# ef01.net
KiCad netlist of a schematic drawn in EAGLE
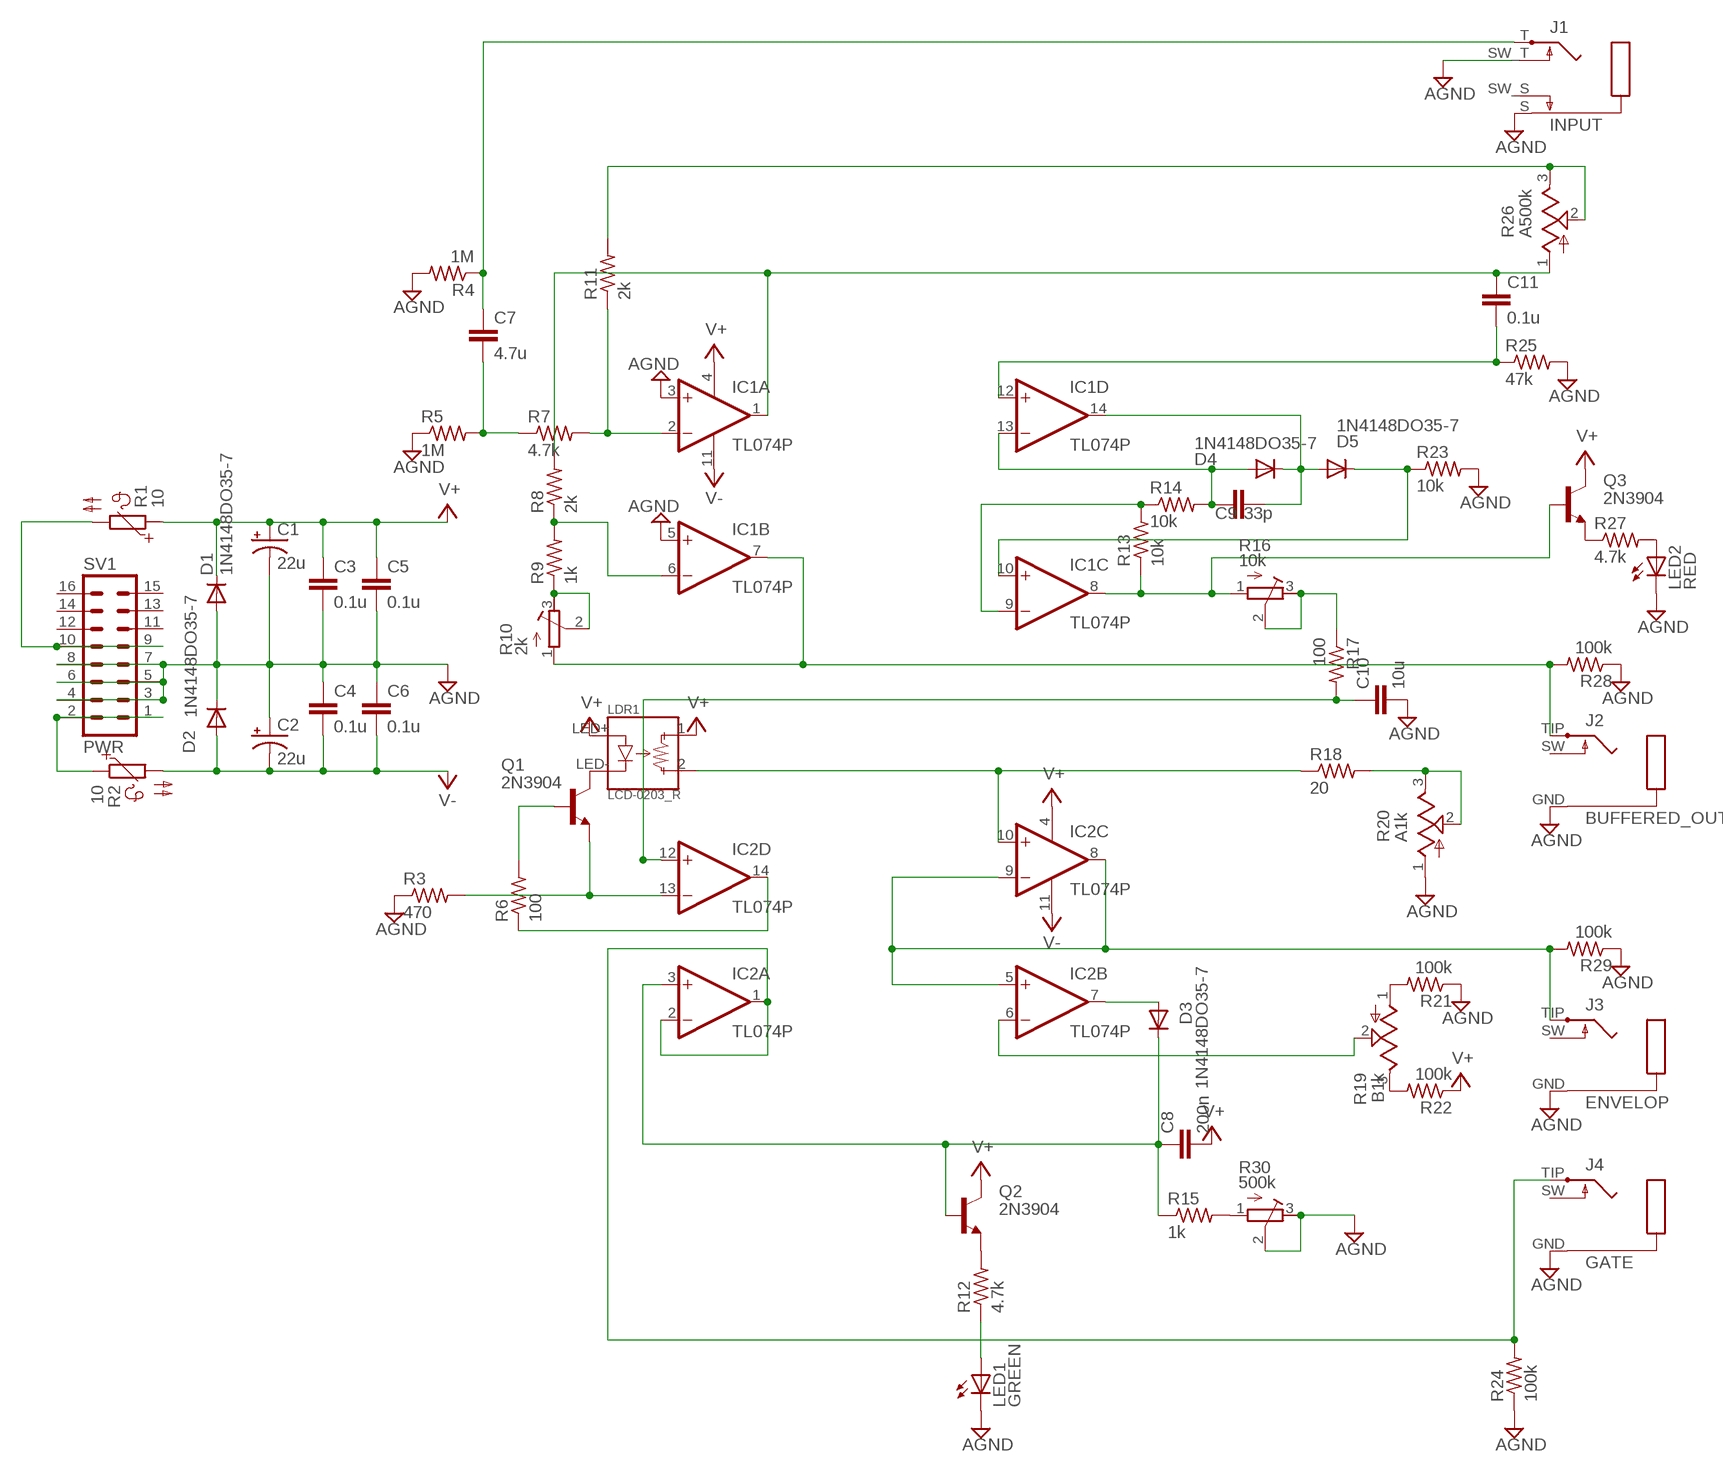
[diagram p0: schematic, sheet 1]

(export (version "E")
  (design (tool "Eeschema 10.0.6"))
  (components
    (comp (ref "C1")
      (value "22u")
      (footprint "eagle-import:E2,5-5")
      (libsource (lib "eagle-import") (part "CPOL-USE2.5-5"))
    )
    (comp (ref "C2")
      (value "22u")
      (footprint "eagle-import:E2,5-5")
      (libsource (lib "eagle-import") (part "CPOL-USE2.5-5"))
    )
    (comp (ref "C3")
      (value "0.1u")
      (footprint "eagle-import:C050-024X044")
      (libsource (lib "eagle-import") (part "C-EU050-024X044"))
    )
    (comp (ref "C4")
      (value "0.1u")
      (footprint "eagle-import:C050-024X044")
      (libsource (lib "eagle-import") (part "C-EU050-024X044"))
    )
    (comp (ref "C5")
      (value "0.1u")
      (footprint "eagle-import:C050-024X044")
      (libsource (lib "eagle-import") (part "C-EU050-024X044"))
    )
    (comp (ref "C6")
      (value "0.1u")
      (footprint "eagle-import:C050-024X044")
      (libsource (lib "eagle-import") (part "C-EU050-024X044"))
    )
    (comp (ref "C7")
      (value "4.7u")
      (footprint "eagle-import:C050-024X044")
      (libsource (lib "eagle-import") (part "C-EU050-024X044"))
    )
    (comp (ref "C8")
      (value "200n")
      (footprint "eagle-import:C050-024X044")
      (libsource (lib "eagle-import") (part "C-EU050-024X044"))
    )
    (comp (ref "C9")
      (value "33p")
      (footprint "eagle-import:C050-024X044")
      (libsource (lib "eagle-import") (part "C-EU050-024X044"))
    )
    (comp (ref "C10")
      (value "10u")
      (footprint "eagle-import:C050-024X044")
      (libsource (lib "eagle-import") (part "C-EU050-024X044"))
    )
    (comp (ref "C11")
      (value "0.1u")
      (footprint "eagle-import:C050-024X044")
      (libsource (lib "eagle-import") (part "C-EU050-024X044"))
    )
    (comp (ref "D1")
      (value "1N4148DO35-7")
      (footprint "eagle-import:DO35-7")
      (libsource (lib "eagle-import") (part "1N4148DO35-7"))
    )
    (comp (ref "D2")
      (value "1N4148DO35-7")
      (footprint "eagle-import:DO35-7")
      (libsource (lib "eagle-import") (part "1N4148DO35-7"))
    )
    (comp (ref "D3")
      (value "1N4148DO35-7")
      (footprint "eagle-import:DO35-7")
      (libsource (lib "eagle-import") (part "1N4148DO35-7"))
    )
    (comp (ref "D4")
      (value "1N4148DO35-7")
      (footprint "eagle-import:DO35-7")
      (libsource (lib "eagle-import") (part "1N4148DO35-7"))
    )
    (comp (ref "D5")
      (value "1N4148DO35-7")
      (footprint "eagle-import:DO35-7")
      (libsource (lib "eagle-import") (part "1N4148DO35-7"))
    )
    (comp (ref "IC1")
      (value "TL074P")
      (footprint "eagle-import:DIL14")
      (libsource (lib "eagle-import") (part "TL074P"))
    )
    (comp (ref "IC2")
      (value "TL074P")
      (footprint "eagle-import:DIL14")
      (libsource (lib "eagle-import") (part "TL074P"))
    )
    (comp (ref "J1")
      (value "INPUT")
      (footprint "eagle-import:ACJM-MHDR")
      (libsource (lib "eagle-import") (part "ACJM-MHDR"))
    )
    (comp (ref "J2")
      (value "BUFFERED_OUT")
      (footprint "eagle-import:35RAPC2AV")
      (libsource (lib "eagle-import") (part "35RAPC2AV"))
    )
    (comp (ref "J3")
      (value "ENVELOP")
      (footprint "eagle-import:35RAPC2AV")
      (libsource (lib "eagle-import") (part "35RAPC2AV"))
    )
    (comp (ref "J4")
      (value "GATE")
      (footprint "eagle-import:35RAPC2AV")
      (libsource (lib "eagle-import") (part "35RAPC2AV"))
    )
    (comp (ref "LDR1")
      (value "LCD-0203_R")
      (footprint "eagle-import:LCD-0203-R")
      (libsource (lib "eagle-import") (part "LCD-0203_R"))
    )
    (comp (ref "LED1")
      (value "GREEN")
      (footprint "eagle-import:LED3MM")
      (libsource (lib "eagle-import") (part "LED3MM"))
    )
    (comp (ref "LED2")
      (value "RED")
      (footprint "eagle-import:LED3MM")
      (libsource (lib "eagle-import") (part "LED3MM"))
    )
    (comp (ref "Q1")
      (value "2N3904")
      (footprint "eagle-import:TO92")
      (libsource (lib "eagle-import") (part "2N3904"))
    )
    (comp (ref "Q2")
      (value "2N3904")
      (footprint "eagle-import:TO92")
      (libsource (lib "eagle-import") (part "2N3904"))
    )
    (comp (ref "Q3")
      (value "2N3904")
      (footprint "eagle-import:TO92")
      (libsource (lib "eagle-import") (part "2N3904"))
    )
    (comp (ref "R1")
      (value "10")
      (footprint "eagle-import:P679")
      (libsource (lib "eagle-import") (part "PTC679"))
    )
    (comp (ref "R2")
      (value "10")
      (footprint "eagle-import:P679")
      (libsource (lib "eagle-import") (part "PTC679"))
    )
    (comp (ref "R3")
      (value "470")
      (footprint "eagle-import:0204_7")
      (libsource (lib "eagle-import") (part "R-US_0204/7"))
    )
    (comp (ref "R4")
      (value "1M")
      (footprint "eagle-import:0204_7")
      (libsource (lib "eagle-import") (part "R-US_0204/7"))
    )
    (comp (ref "R5")
      (value "1M")
      (footprint "eagle-import:0204_7")
      (libsource (lib "eagle-import") (part "R-US_0204/7"))
    )
    (comp (ref "R6")
      (value "100")
      (footprint "eagle-import:0204_7")
      (libsource (lib "eagle-import") (part "R-US_0204/7"))
    )
    (comp (ref "R7")
      (value "4.7k")
      (footprint "eagle-import:0204_7")
      (libsource (lib "eagle-import") (part "R-US_0204/7"))
    )
    (comp (ref "R8")
      (value "2k")
      (footprint "eagle-import:0204_7")
      (libsource (lib "eagle-import") (part "R-US_0204/7"))
    )
    (comp (ref "R9")
      (value "1k")
      (footprint "eagle-import:0204_7")
      (libsource (lib "eagle-import") (part "R-US_0204/7"))
    )
    (comp (ref "R10")
      (value "2k")
      (footprint "eagle-import:GF063P")
      (libsource (lib "eagle-import") (part "GFP063P"))
    )
    (comp (ref "R11")
      (value "2k")
      (footprint "eagle-import:0204_7")
      (libsource (lib "eagle-import") (part "R-US_0204/7"))
    )
    (comp (ref "R12")
      (value "4.7k")
      (footprint "eagle-import:0204_7")
      (libsource (lib "eagle-import") (part "R-US_0204/7"))
    )
    (comp (ref "R13")
      (value "10k")
      (footprint "eagle-import:0204_7")
      (libsource (lib "eagle-import") (part "R-US_0204/7"))
    )
    (comp (ref "R14")
      (value "10k")
      (footprint "eagle-import:0204_7")
      (libsource (lib "eagle-import") (part "R-US_0204/7"))
    )
    (comp (ref "R15")
      (value "1k")
      (footprint "eagle-import:0204_7")
      (libsource (lib "eagle-import") (part "R-US_0204/7"))
    )
    (comp (ref "R16")
      (value "10k")
      (footprint "eagle-import:GF063P")
      (libsource (lib "eagle-import") (part "GFP063P"))
    )
    (comp (ref "R17")
      (value "100")
      (footprint "eagle-import:0204_7")
      (libsource (lib "eagle-import") (part "R-US_0204/7"))
    )
    (comp (ref "R18")
      (value "20")
      (footprint "eagle-import:0204_7")
      (libsource (lib "eagle-import") (part "R-US_0204/7"))
    )
    (comp (ref "R19")
      (value "B1k")
      (footprint "eagle-import:RK097111")
      (libsource (lib "eagle-import") (part "RK097111"))
    )
    (comp (ref "R20")
      (value "A1k")
      (footprint "eagle-import:RK097111")
      (libsource (lib "eagle-import") (part "RK097111"))
    )
    (comp (ref "R21")
      (value "100k")
      (footprint "eagle-import:0204_7")
      (libsource (lib "eagle-import") (part "R-US_0204/7"))
    )
    (comp (ref "R22")
      (value "100k")
      (footprint "eagle-import:0204_7")
      (libsource (lib "eagle-import") (part "R-US_0204/7"))
    )
    (comp (ref "R23")
      (value "10k")
      (footprint "eagle-import:0204_7")
      (libsource (lib "eagle-import") (part "R-US_0204/7"))
    )
    (comp (ref "R24")
      (value "100k")
      (footprint "eagle-import:0204_7")
      (libsource (lib "eagle-import") (part "R-US_0204/7"))
    )
    (comp (ref "R25")
      (value "47k")
      (footprint "eagle-import:0204_7")
      (libsource (lib "eagle-import") (part "R-US_0204/7"))
    )
    (comp (ref "R26")
      (value "A500k")
      (footprint "eagle-import:RK097111")
      (libsource (lib "eagle-import") (part "RK097111"))
    )
    (comp (ref "R27")
      (value "4.7k")
      (footprint "eagle-import:0204_7")
      (libsource (lib "eagle-import") (part "R-US_0204/7"))
    )
    (comp (ref "R28")
      (value "100k")
      (footprint "eagle-import:0204_7")
      (libsource (lib "eagle-import") (part "R-US_0204/7"))
    )
    (comp (ref "R29")
      (value "100k")
      (footprint "eagle-import:0204_7")
      (libsource (lib "eagle-import") (part "R-US_0204/7"))
    )
    (comp (ref "R30")
      (value "500k")
      (footprint "eagle-import:GF063P")
      (libsource (lib "eagle-import") (part "GFP063P"))
    )
    (comp (ref "SV1")
      (value "PWR")
      (footprint "eagle-import:ML16")
      (libsource (lib "eagle-import") (part "ML16"))
    )
  )
  (nets
    (net (code "1") (name "AGND") (class "Default")
      (node (ref "C1") (pin "-") (pinfunction "-_-") (pintype "passive"))
      (node (ref "C10") (pin "2") (pinfunction "2_2") (pintype "passive"))
      (node (ref "C2") (pin "+") (pinfunction "+_+") (pintype "passive"))
      (node (ref "C3") (pin "2") (pinfunction "2_2") (pintype "passive"))
      (node (ref "C4") (pin "1") (pinfunction "1_1") (pintype "passive"))
      (node (ref "C5") (pin "2") (pinfunction "2_2") (pintype "passive"))
      (node (ref "C6") (pin "1") (pinfunction "1_1") (pintype "passive"))
      (node (ref "D1") (pin "A") (pinfunction "A_A") (pintype "passive"))
      (node (ref "D2") (pin "C") (pinfunction "C_C") (pintype "passive"))
      (node (ref "IC1") (pin "3") (pinfunction "+IN_3") (pintype "input"))
      (node (ref "IC1") (pin "5") (pinfunction "+IN_5") (pintype "input"))
      (node (ref "J1") (pin "S") (pinfunction "GND_S") (pintype "passive"))
      (node (ref "J1") (pin "SW_T") (pinfunction "T_SW_SW_T") (pintype "passive"))
      (node (ref "J2") (pin "GND") (pinfunction "GND_GND") (pintype "passive"))
      (node (ref "J3") (pin "GND") (pinfunction "GND_GND") (pintype "passive"))
      (node (ref "J4") (pin "GND") (pinfunction "GND_GND") (pintype "passive"))
      (node (ref "LED1") (pin "K") (pinfunction "C_K") (pintype "passive"))
      (node (ref "LED2") (pin "K") (pinfunction "C_K") (pintype "passive"))
      (node (ref "R20") (pin "1") (pinfunction "1_1") (pintype "passive"))
      (node (ref "R21") (pin "1") (pinfunction "1_1") (pintype "passive"))
      (node (ref "R23") (pin "2") (pinfunction "2_2") (pintype "passive"))
      (node (ref "R24") (pin "1") (pinfunction "1_1") (pintype "passive"))
      (node (ref "R25") (pin "2") (pinfunction "2_2") (pintype "passive"))
      (node (ref "R28") (pin "1") (pinfunction "1_1") (pintype "passive"))
      (node (ref "R29") (pin "1") (pinfunction "1_1") (pintype "passive"))
      (node (ref "R3") (pin "1") (pinfunction "1_1") (pintype "passive"))
      (node (ref "R30") (pin "2") (pinfunction "2_2") (pintype "passive"))
      (node (ref "R30") (pin "3") (pinfunction "3_3") (pintype "passive"))
      (node (ref "R4") (pin "2") (pinfunction "2_2") (pintype "passive"))
      (node (ref "R5") (pin "1") (pinfunction "1_1") (pintype "passive"))
      (node (ref "SV1") (pin "3") (pinfunction "3_3") (pintype "passive"))
      (node (ref "SV1") (pin "4") (pinfunction "4_4") (pintype "passive"))
      (node (ref "SV1") (pin "5") (pinfunction "5_5") (pintype "passive"))
      (node (ref "SV1") (pin "6") (pinfunction "6_6") (pintype "passive"))
      (node (ref "SV1") (pin "7") (pinfunction "7_7") (pintype "passive"))
      (node (ref "SV1") (pin "8") (pinfunction "8_8") (pintype "passive"))
    )
    (net (code "2") (name "Net-(C7-Pad2)") (class "Default")
      (node (ref "C7") (pin "2") (pinfunction "2_2") (pintype "passive"))
      (node (ref "R5") (pin "2") (pinfunction "2_2") (pintype "passive"))
      (node (ref "R7") (pin "1") (pinfunction "1_1") (pintype "passive"))
    )
    (net (code "3") (name "Net-(IC1A--IN)") (class "Default")
      (node (ref "IC1") (pin "2") (pinfunction "-IN_2") (pintype "input"))
      (node (ref "R11") (pin "1") (pinfunction "1_1") (pintype "passive"))
      (node (ref "R7") (pin "2") (pinfunction "2_2") (pintype "passive"))
    )
    (net (code "4") (name "Net-(IC1A-OUT)") (class "Default")
      (node (ref "C11") (pin "1") (pinfunction "1_1") (pintype "passive"))
      (node (ref "IC1") (pin "1") (pinfunction "OUT_1") (pintype "output"))
      (node (ref "R26") (pin "1") (pinfunction "1_1") (pintype "passive"))
      (node (ref "R8") (pin "2") (pinfunction "2_2") (pintype "passive"))
    )
    (net (code "5") (name "Net-(IC1B--IN)") (class "Default")
      (node (ref "IC1") (pin "6") (pinfunction "-IN_6") (pintype "input"))
      (node (ref "R8") (pin "1") (pinfunction "1_1") (pintype "passive"))
      (node (ref "R9") (pin "2") (pinfunction "2_2") (pintype "passive"))
    )
    (net (code "6") (name "Net-(IC1B-OUT)") (class "Default")
      (node (ref "IC1") (pin "7") (pinfunction "OUT_7") (pintype "output"))
      (node (ref "J2") (pin "TIP") (pinfunction "TIP_TIP") (pintype "passive"))
      (node (ref "R10") (pin "1") (pinfunction "1_1") (pintype "passive"))
      (node (ref "R28") (pin "2") (pinfunction "2_2") (pintype "passive"))
    )
    (net (code "7") (name "Net-(IC1C-+IN)") (class "Default")
      (node (ref "D5") (pin "C") (pinfunction "C_C") (pintype "passive"))
      (node (ref "IC1") (pin "10") (pinfunction "+IN_10") (pintype "input"))
      (node (ref "R23") (pin "1") (pinfunction "1_1") (pintype "passive"))
    )
    (net (code "8") (name "Net-(IC1C--IN)") (class "Default")
      (node (ref "IC1") (pin "9") (pinfunction "-IN_9") (pintype "input"))
      (node (ref "R13") (pin "2") (pinfunction "2_2") (pintype "passive"))
      (node (ref "R14") (pin "1") (pinfunction "1_1") (pintype "passive"))
    )
    (net (code "9") (name "Net-(IC1C-OUT)") (class "Default")
      (node (ref "IC1") (pin "8") (pinfunction "OUT_8") (pintype "output"))
      (node (ref "Q3") (pin "2") (pinfunction "B_2") (pintype "passive"))
      (node (ref "R13") (pin "1") (pinfunction "1_1") (pintype "passive"))
      (node (ref "R16") (pin "1") (pinfunction "1_1") (pintype "passive"))
    )
    (net (code "10") (name "Net-(IC1D-+IN)") (class "Default")
      (node (ref "C11") (pin "2") (pinfunction "2_2") (pintype "passive"))
      (node (ref "IC1") (pin "12") (pinfunction "+IN_12") (pintype "input"))
      (node (ref "R25") (pin "1") (pinfunction "1_1") (pintype "passive"))
    )
    (net (code "11") (name "Net-(IC1D--IN)") (class "Default")
      (node (ref "C9") (pin "1") (pinfunction "1_1") (pintype "passive"))
      (node (ref "D4") (pin "A") (pinfunction "A_A") (pintype "passive"))
      (node (ref "IC1") (pin "13") (pinfunction "-IN_13") (pintype "input"))
      (node (ref "R14") (pin "2") (pinfunction "2_2") (pintype "passive"))
    )
    (net (code "12") (name "Net-(IC1D-OUT)") (class "Default")
      (node (ref "C9") (pin "2") (pinfunction "2_2") (pintype "passive"))
      (node (ref "D4") (pin "C") (pinfunction "C_C") (pintype "passive"))
      (node (ref "D5") (pin "A") (pinfunction "A_A") (pintype "passive"))
      (node (ref "IC1") (pin "14") (pinfunction "OUT_14") (pintype "output"))
    )
    (net (code "13") (name "Net-(IC2A-+IN)") (class "Default")
      (node (ref "C8") (pin "1") (pinfunction "1_1") (pintype "passive"))
      (node (ref "D3") (pin "C") (pinfunction "C_C") (pintype "passive"))
      (node (ref "IC2") (pin "3") (pinfunction "+IN_3") (pintype "input"))
      (node (ref "Q2") (pin "2") (pinfunction "B_2") (pintype "passive"))
      (node (ref "R15") (pin "1") (pinfunction "1_1") (pintype "passive"))
    )
    (net (code "14") (name "Net-(IC2A--IN)") (class "Default")
      (node (ref "IC2") (pin "1") (pinfunction "OUT_1") (pintype "output"))
      (node (ref "IC2") (pin "2") (pinfunction "-IN_2") (pintype "input"))
      (node (ref "J4") (pin "TIP") (pinfunction "TIP_TIP") (pintype "passive"))
      (node (ref "R24") (pin "2") (pinfunction "2_2") (pintype "passive"))
    )
    (net (code "15") (name "Net-(IC2B-+IN)") (class "Default")
      (node (ref "IC2") (pin "5") (pinfunction "+IN_5") (pintype "input"))
      (node (ref "IC2") (pin "8") (pinfunction "OUT_8") (pintype "output"))
      (node (ref "IC2") (pin "9") (pinfunction "-IN_9") (pintype "input"))
      (node (ref "J3") (pin "TIP") (pinfunction "TIP_TIP") (pintype "passive"))
      (node (ref "R29") (pin "2") (pinfunction "2_2") (pintype "passive"))
    )
    (net (code "16") (name "Net-(IC2B--IN)") (class "Default")
      (node (ref "IC2") (pin "6") (pinfunction "-IN_6") (pintype "input"))
      (node (ref "R19") (pin "2") (pinfunction "2_2") (pintype "passive"))
    )
    (net (code "17") (name "Net-(IC2B-OUT)") (class "Default")
      (node (ref "D3") (pin "A") (pinfunction "A_A") (pintype "passive"))
      (node (ref "IC2") (pin "7") (pinfunction "OUT_7") (pintype "output"))
    )
    (net (code "18") (name "Net-(IC2C-+IN)") (class "Default")
      (node (ref "IC2") (pin "10") (pinfunction "+IN_10") (pintype "input"))
      (node (ref "LDR1") (pin "2") (pinfunction "2_2") (pintype "passive"))
      (node (ref "R18") (pin "1") (pinfunction "1_1") (pintype "passive"))
    )
    (net (code "19") (name "Net-(IC2D-+IN)") (class "Default")
      (node (ref "C10") (pin "1") (pinfunction "1_1") (pintype "passive"))
      (node (ref "IC2") (pin "12") (pinfunction "+IN_12") (pintype "input"))
      (node (ref "R17") (pin "2") (pinfunction "2_2") (pintype "passive"))
    )
    (net (code "20") (name "Net-(IC2D--IN)") (class "Default")
      (node (ref "IC2") (pin "13") (pinfunction "-IN_13") (pintype "input"))
      (node (ref "Q1") (pin "3") (pinfunction "E_3") (pintype "passive"))
      (node (ref "R3") (pin "2") (pinfunction "2_2") (pintype "passive"))
    )
    (net (code "21") (name "Net-(IC2D-OUT)") (class "Default")
      (node (ref "IC2") (pin "14") (pinfunction "OUT_14") (pintype "output"))
      (node (ref "R6") (pin "1") (pinfunction "1_1") (pintype "passive"))
    )
    (net (code "22") (name "Net-(J1-TIP)") (class "Default")
      (node (ref "C7") (pin "1") (pinfunction "1_1") (pintype "passive"))
      (node (ref "J1") (pin "T") (pinfunction "TIP_T") (pintype "passive"))
      (node (ref "R4") (pin "1") (pinfunction "1_1") (pintype "passive"))
    )
    (net (code "23") (name "Net-(LDR1-D-)") (class "Default")
      (node (ref "LDR1") (pin "LED-") (pinfunction "D-_LED-") (pintype "passive"))
      (node (ref "Q1") (pin "1") (pinfunction "C_1") (pintype "passive"))
    )
    (net (code "24") (name "Net-(LED1-PadA)") (class "Default")
      (node (ref "LED1") (pin "A") (pinfunction "A_A") (pintype "passive"))
      (node (ref "R12") (pin "1") (pinfunction "1_1") (pintype "passive"))
    )
    (net (code "25") (name "Net-(LED2-PadA)") (class "Default")
      (node (ref "LED2") (pin "A") (pinfunction "A_A") (pintype "passive"))
      (node (ref "R27") (pin "2") (pinfunction "2_2") (pintype "passive"))
    )
    (net (code "26") (name "Net-(Q1-B)") (class "Default")
      (node (ref "Q1") (pin "2") (pinfunction "B_2") (pintype "passive"))
      (node (ref "R6") (pin "2") (pinfunction "2_2") (pintype "passive"))
    )
    (net (code "27") (name "Net-(Q2-E)") (class "Default")
      (node (ref "Q2") (pin "3") (pinfunction "E_3") (pintype "passive"))
      (node (ref "R12") (pin "2") (pinfunction "2_2") (pintype "passive"))
    )
    (net (code "28") (name "Net-(Q3-E)") (class "Default")
      (node (ref "Q3") (pin "3") (pinfunction "E_3") (pintype "passive"))
      (node (ref "R27") (pin "1") (pinfunction "1_1") (pintype "passive"))
    )
    (net (code "29") (name "Net-(R1-Pad2)") (class "Default")
      (node (ref "R1") (pin "2") (pinfunction "2_2") (pintype "passive"))
      (node (ref "SV1") (pin "10") (pinfunction "10_10") (pintype "passive"))
      (node (ref "SV1") (pin "9") (pinfunction "9_9") (pintype "passive"))
    )
    (net (code "30") (name "Net-(R2-Pad1)") (class "Default")
      (node (ref "R2") (pin "1") (pinfunction "1_1") (pintype "passive"))
      (node (ref "SV1") (pin "1") (pinfunction "1_1") (pintype "passive"))
      (node (ref "SV1") (pin "2") (pinfunction "2_2") (pintype "passive"))
    )
    (net (code "31") (name "Net-(R10-Pad2)") (class "Default")
      (node (ref "R10") (pin "2") (pinfunction "2_2") (pintype "passive"))
      (node (ref "R10") (pin "3") (pinfunction "3_3") (pintype "passive"))
      (node (ref "R9") (pin "1") (pinfunction "1_1") (pintype "passive"))
    )
    (net (code "32") (name "Net-(R11-Pad2)") (class "Default")
      (node (ref "R11") (pin "2") (pinfunction "2_2") (pintype "passive"))
      (node (ref "R26") (pin "2") (pinfunction "2_2") (pintype "passive"))
      (node (ref "R26") (pin "3") (pinfunction "3_3") (pintype "passive"))
    )
    (net (code "33") (name "Net-(R15-Pad2)") (class "Default")
      (node (ref "R15") (pin "2") (pinfunction "2_2") (pintype "passive"))
      (node (ref "R30") (pin "1") (pinfunction "1_1") (pintype "passive"))
    )
    (net (code "34") (name "Net-(R16-Pad2)") (class "Default")
      (node (ref "R16") (pin "2") (pinfunction "2_2") (pintype "passive"))
      (node (ref "R16") (pin "3") (pinfunction "3_3") (pintype "passive"))
      (node (ref "R17") (pin "1") (pinfunction "1_1") (pintype "passive"))
    )
    (net (code "35") (name "Net-(R18-Pad2)") (class "Default")
      (node (ref "R18") (pin "2") (pinfunction "2_2") (pintype "passive"))
      (node (ref "R20") (pin "2") (pinfunction "2_2") (pintype "passive"))
      (node (ref "R20") (pin "3") (pinfunction "3_3") (pintype "passive"))
    )
    (net (code "36") (name "Net-(R19-Pad1)") (class "Default")
      (node (ref "R19") (pin "1") (pinfunction "1_1") (pintype "passive"))
      (node (ref "R21") (pin "2") (pinfunction "2_2") (pintype "passive"))
    )
    (net (code "37") (name "Net-(R19-Pad3)") (class "Default")
      (node (ref "R19") (pin "3") (pinfunction "3_3") (pintype "passive"))
      (node (ref "R22") (pin "2") (pinfunction "2_2") (pintype "passive"))
    )
    (net (code "38") (name "V+") (class "Default")
      (node (ref "C1") (pin "+") (pinfunction "+_+") (pintype "passive"))
      (node (ref "C3") (pin "1") (pinfunction "1_1") (pintype "passive"))
      (node (ref "C5") (pin "1") (pinfunction "1_1") (pintype "passive"))
      (node (ref "C8") (pin "2") (pinfunction "2_2") (pintype "passive"))
      (node (ref "D1") (pin "C") (pinfunction "C_C") (pintype "passive"))
      (node (ref "IC1") (pin "4") (pinfunction "V+_4") (pintype "power_in"))
      (node (ref "IC2") (pin "4") (pinfunction "V+_4") (pintype "power_in"))
      (node (ref "LDR1") (pin "1") (pinfunction "1_1") (pintype "passive"))
      (node (ref "LDR1") (pin "LED+") (pinfunction "D+_LED+") (pintype "passive"))
      (node (ref "Q2") (pin "1") (pinfunction "C_1") (pintype "passive"))
      (node (ref "Q3") (pin "1") (pinfunction "C_1") (pintype "passive"))
      (node (ref "R1") (pin "1") (pinfunction "1_1") (pintype "passive"))
      (node (ref "R22") (pin "1") (pinfunction "1_1") (pintype "passive"))
    )
    (net (code "39") (name "V-") (class "Default")
      (node (ref "C2") (pin "-") (pinfunction "-_-") (pintype "passive"))
      (node (ref "C4") (pin "2") (pinfunction "2_2") (pintype "passive"))
      (node (ref "C6") (pin "2") (pinfunction "2_2") (pintype "passive"))
      (node (ref "D2") (pin "A") (pinfunction "A_A") (pintype "passive"))
      (node (ref "IC1") (pin "11") (pinfunction "V-_11") (pintype "power_in"))
      (node (ref "IC2") (pin "11") (pinfunction "V-_11") (pintype "power_in"))
      (node (ref "R2") (pin "2") (pinfunction "2_2") (pintype "passive"))
    )
    (net (code "40") (name "unconnected-(J1-SW_G-PadSW_S)") (class "Default")
      (node (ref "J1") (pin "SW_S") (pinfunction "SW_G_SW_S") (pintype "passive"))
    )
    (net (code "41") (name "unconnected-(J2-PadSW)") (class "Default")
      (node (ref "J2") (pin "SW") (pinfunction "SW_SW") (pintype "passive"))
    )
    (net (code "42") (name "unconnected-(J3-PadSW)") (class "Default")
      (node (ref "J3") (pin "SW") (pinfunction "SW_SW") (pintype "passive"))
    )
    (net (code "43") (name "unconnected-(J4-PadSW)") (class "Default")
      (node (ref "J4") (pin "SW") (pinfunction "SW_SW") (pintype "passive"))
    )
    (net (code "44") (name "unconnected-(SV1-Pad11)") (class "Default")
      (node (ref "SV1") (pin "11") (pinfunction "11_11") (pintype "passive"))
    )
    (net (code "45") (name "unconnected-(SV1-Pad12)") (class "Default")
      (node (ref "SV1") (pin "12") (pinfunction "12_12") (pintype "passive"))
    )
    (net (code "46") (name "unconnected-(SV1-Pad13)") (class "Default")
      (node (ref "SV1") (pin "13") (pinfunction "13_13") (pintype "passive"))
    )
    (net (code "47") (name "unconnected-(SV1-Pad14)") (class "Default")
      (node (ref "SV1") (pin "14") (pinfunction "14_14") (pintype "passive"))
    )
    (net (code "48") (name "unconnected-(SV1-Pad15)") (class "Default")
      (node (ref "SV1") (pin "15") (pinfunction "15_15") (pintype "passive"))
    )
    (net (code "49") (name "unconnected-(SV1-Pad16)") (class "Default")
      (node (ref "SV1") (pin "16") (pinfunction "16_16") (pintype "passive"))
    )
  )
)
